# MCU1.net
KiCad netlist of a schematic drawn in Altium Designer
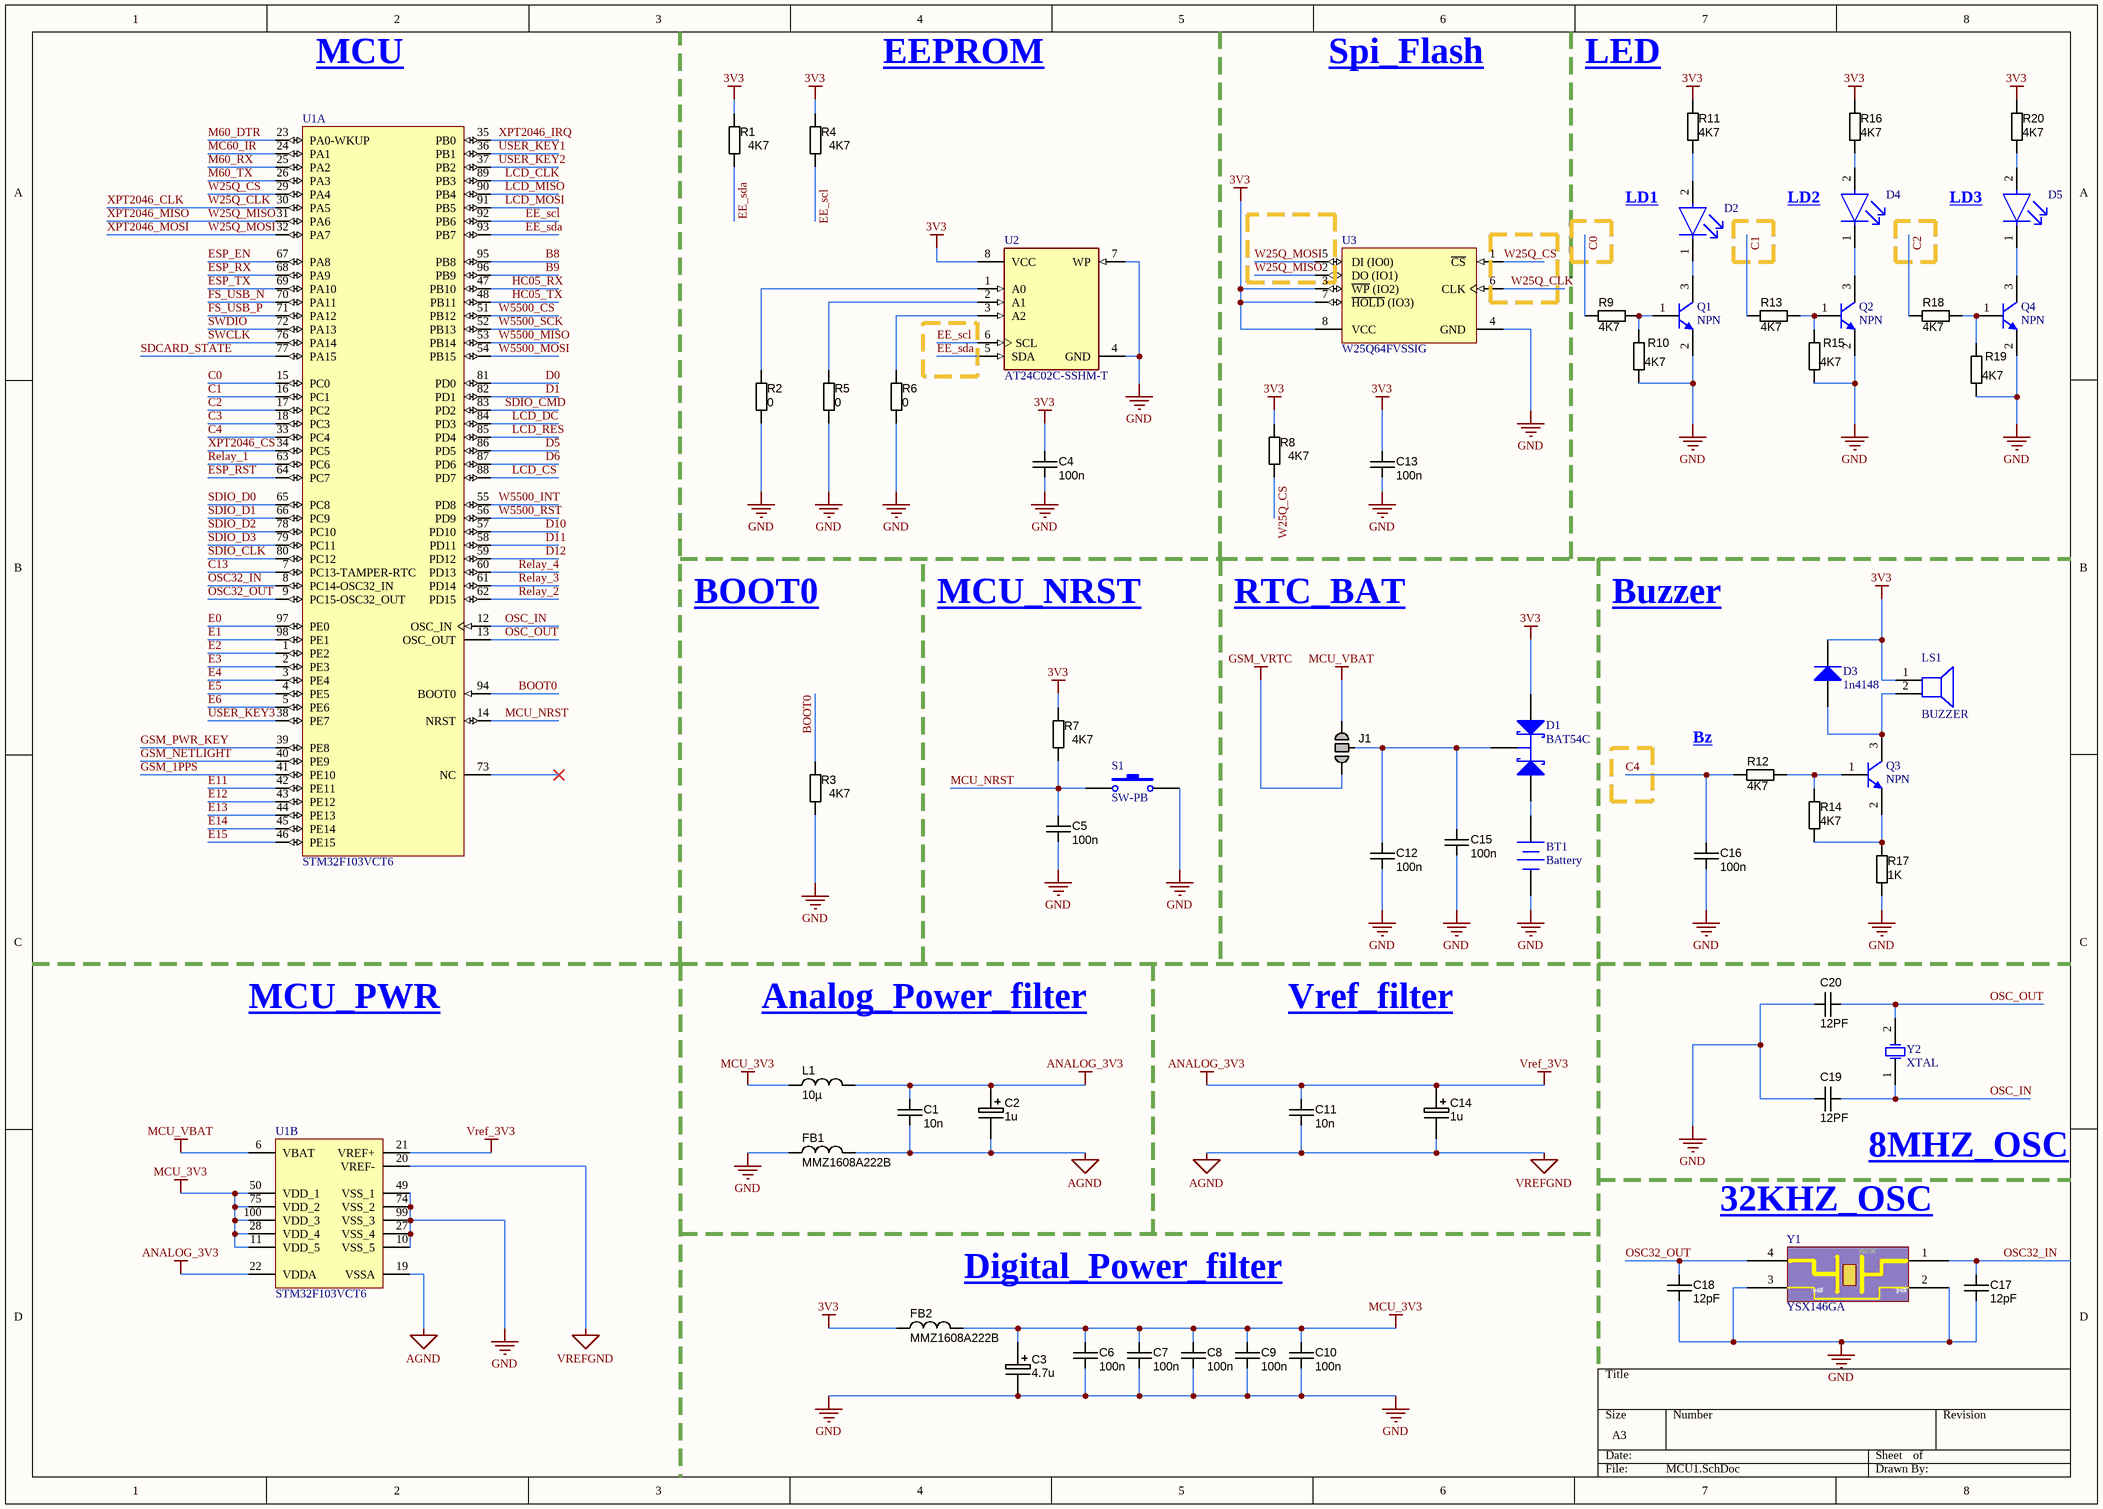
[diagram p0: MCU1.SchDoc]

(export (version "E")
  (design (tool "Eeschema 10.0.6"))
  (components
    (comp (ref "BT1")
      (value "Battery")
      (footprint "BTH1220")
      (description "Multicell Battery")
      (fields (field (name "PUBLISHER") "Altium Limited"))
      (libsource (lib "Miscellaneous Devices") (part "Battery"))
    )
    (comp (ref "C1")
      (value "10n")
      (footprint "CAPC1608X90N")
      (description "Capacitor SMD Cer 100nF 10% 50V X7R 0603")
      (fields (field (name "TOLERANCE") "±10%") (field (name "Comment") "approved sub OK"))
      (libsource (lib "PBL - Capacitors") (part "CAPC_100n_0603_X7R_50V_10%"))
    )
    (comp (ref "C2")
      (value "1u")
      (footprint "C_TN_3216")
      (description "Capacitor SMD Tantalum 10uF 10% 16V 3216-18")
      (fields (field (name "TOLERANCE") "±10%"))
      (libsource (lib "PBL - Capacitors") (part "CAPT_4u7_3216_16V"))
    )
    (comp (ref "C3")
      (value "4.7u")
      (footprint "C_TN_3528")
      (description "Capacitor SMD Tantalum 10uF 10% 16V 3216-18")
      (fields (field (name "TOLERANCE") "±10%"))
      (libsource (lib "PBL - Capacitors") (part "CAPT_4u7_3216_16V"))
    )
    (comp (ref "C4")
      (value "100n")
      (footprint "CAPC1608X90N")
      (description "Capacitor SMD Cer 100nF 10% 50V X7R 0603")
      (fields (field (name "TOLERANCE") "±10%") (field (name "Comment") "approved sub OK"))
      (libsource (lib "PBL - Capacitors") (part "CAPC_100n_0603_X7R_50V_10%"))
    )
    (comp (ref "C5")
      (value "100n")
      (footprint "CAPC1608X90N")
      (description "Capacitor SMD Cer 100nF 10% 50V X7R 0603")
      (fields (field (name "TOLERANCE") "±10%") (field (name "Comment") "approved sub OK"))
      (libsource (lib "PBL - Capacitors") (part "CAPC_100n_0603_X7R_50V_10%"))
    )
    (comp (ref "C6")
      (value "100n")
      (footprint "CAPC1608X90N")
      (description "Capacitor SMD Cer 100nF 10% 50V X7R 0603")
      (fields (field (name "TOLERANCE") "±10%") (field (name "Comment") "approved sub OK"))
      (libsource (lib "PBL - Capacitors") (part "CAPC_100n_0603_X7R_50V_10%"))
    )
    (comp (ref "C7")
      (value "100n")
      (footprint "CAPC1608X90N")
      (description "Capacitor SMD Cer 100nF 10% 50V X7R 0603")
      (fields (field (name "TOLERANCE") "±10%") (field (name "Comment") "approved sub OK"))
      (libsource (lib "PBL - Capacitors") (part "CAPC_100n_0603_X7R_50V_10%"))
    )
    (comp (ref "C8")
      (value "100n")
      (footprint "CAPC1608X90N")
      (description "Capacitor SMD Cer 100nF 10% 50V X7R 0603")
      (fields (field (name "TOLERANCE") "±10%") (field (name "Comment") "approved sub OK"))
      (libsource (lib "PBL - Capacitors") (part "CAPC_100n_0603_X7R_50V_10%"))
    )
    (comp (ref "C9")
      (value "100n")
      (footprint "CAPC1608X90N")
      (description "Capacitor SMD Cer 100nF 10% 50V X7R 0603")
      (fields (field (name "TOLERANCE") "±10%") (field (name "Comment") "approved sub OK"))
      (libsource (lib "PBL - Capacitors") (part "CAPC_100n_0603_X7R_50V_10%"))
    )
    (comp (ref "C10")
      (value "100n")
      (footprint "CAPC1608X90N")
      (description "Capacitor SMD Cer 100nF 10% 50V X7R 0603")
      (fields (field (name "TOLERANCE") "±10%") (field (name "Comment") "approved sub OK"))
      (libsource (lib "PBL - Capacitors") (part "CAPC_100n_0603_X7R_50V_10%"))
    )
    (comp (ref "C11")
      (value "10n")
      (footprint "CAPC1608X90N")
      (description "Capacitor SMD Cer 100nF 10% 50V X7R 0603")
      (fields (field (name "TOLERANCE") "±10%") (field (name "Comment") "approved sub OK"))
      (libsource (lib "PBL - Capacitors") (part "CAPC_100n_0603_X7R_50V_10%"))
    )
    (comp (ref "C12")
      (value "100n")
      (footprint "CAPC1608X90N")
      (description "Capacitor SMD Cer 100nF 10% 50V X7R 0603")
      (fields (field (name "TOLERANCE") "±10%") (field (name "Comment") "approved sub OK"))
      (libsource (lib "PBL - Capacitors") (part "CAPC_100n_0603_X7R_50V_10%"))
    )
    (comp (ref "C13")
      (value "100n")
      (footprint "CAPC1608X90N")
      (description "Capacitor SMD Cer 100nF 10% 50V X7R 0603")
      (fields (field (name "TOLERANCE") "±10%") (field (name "Comment") "approved sub OK"))
      (libsource (lib "PBL - Capacitors") (part "CAPC_100n_0603_X7R_50V_10%"))
    )
    (comp (ref "C14")
      (value "1u")
      (footprint "C_TN_3216")
      (description "Capacitor SMD Tantalum 10uF 10% 16V 3216-18")
      (fields (field (name "TOLERANCE") "±10%"))
      (libsource (lib "PBL - Capacitors") (part "CAPT_4u7_3216_16V"))
    )
    (comp (ref "C15")
      (value "100n")
      (footprint "C1206")
      (description "Capacitor SMD Cer 100nF 10% 50V X7R 0603")
      (fields (field (name "TOLERANCE") "±10%") (field (name "Comment") "approved sub OK"))
      (libsource (lib "PBL - Capacitors") (part "CAPC_100n_0603_X7R_50V_10%"))
    )
    (comp (ref "C16")
      (value "100n")
      (footprint "CAPC1608X90N")
      (description "Capacitor SMD Cer 100nF 10% 50V X7R 0603")
      (fields (field (name "TOLERANCE") "±10%") (field (name "Comment") "approved sub OK"))
      (libsource (lib "PBL - Capacitors") (part "CAPC_100n_0603_X7R_50V_10%"))
    )
    (comp (ref "C17")
      (value "12pF")
      (footprint "CAPC1608X90N")
      (description "Capacitor SMD Cer 6.8PF 10% 50V X7R 0603")
      (fields (field (name "TOLERANCE") "±10%") (field (name "Comment") "approved sub OK"))
      (libsource (lib "PBL - Capacitors") (part "CAPC_100n_0603_X7R_50V_10%"))
    )
    (comp (ref "C18")
      (value "12pF")
      (footprint "CAPC1608X90N")
      (description "Capacitor SMD Cer 6.8PF 10% 50V X7R 0603")
      (fields (field (name "TOLERANCE") "±10%") (field (name "Comment") "approved sub OK"))
      (libsource (lib "PBL - Capacitors") (part "CAPC_100n_0603_X7R_50V_10%"))
    )
    (comp (ref "C19")
      (value "12PF")
      (footprint "CAPC1608X90N")
      (description "Capacitor SMD Cer 20PF10% 50V X7R 0603")
      (fields (field (name "TOLERANCE") "±10%") (field (name "Comment") "approved sub OK"))
      (libsource (lib "PBL - Capacitors") (part "CAPC_100n_0603_X7R_50V_10%"))
    )
    (comp (ref "C20")
      (value "12PF")
      (footprint "CAPC1608X90N")
      (description "Capacitor SMD Cer 20PF10% 50V X7R 0603")
      (fields (field (name "TOLERANCE") "±10%") (field (name "Comment") "approved sub OK"))
      (libsource (lib "PBL - Capacitors") (part "CAPC_100n_0603_X7R_50V_10%"))
    )
    (comp (ref "D1")
      (value "BAT54C")
      (footprint "NXP-SOT23-3_V")
      (description "Schottky Barrier Diode, 30 V, 2 uA, -55 to 150 degC, 3-Pin SOT23, RoHS, Tape and Reel")
      (fields (field (name "MANUFACTURER") "NXP Semiconductors"))
      (libsource (lib "Altium Content Vault") (part "NXP-DSKY_A1A2K3-3"))
    )
    (comp (ref "D2")
      (value "LTST-C191TBKT")
      (footprint "FP-LTST-C191TBKT-MFG")
      (description "LED BLUE CLEAR CHIP SMD")
      (libsource (lib "Altium Content Vault") (part "8706943c75ba83719d021d2fdc84c58"))
    )
    (comp (ref "D3")
      (value "1n4148")
      (footprint "d_sod80")
      (description "Default Diode")
      (fields (field (name "PUBLISHER") "Altium Limited"))
      (libsource (lib "Miscellaneous Devices") (part "Diode"))
    )
    (comp (ref "D4")
      (value "LTST-C191TBKT")
      (footprint "FP-LTST-C191TBKT-MFG")
      (description "LED BLUE CLEAR CHIP SMD")
      (libsource (lib "Altium Content Vault") (part "8706943c75ba83719d021d2fdc84c58"))
    )
    (comp (ref "D5")
      (value "LTST-C191TBKT")
      (footprint "FP-LTST-C191TBKT-MFG")
      (description "LED BLUE CLEAR CHIP SMD")
      (libsource (lib "Altium Content Vault") (part "8706943c75ba83719d021d2fdc84c58"))
    )
    (comp (ref "FB1")
      (value "2K2 @ 100 MHz")
      (footprint "FBC1608X95N")
      (description "Ferrite bead 2.2K Ohm at 100 MHz 200mA 0603 SMD")
      (fields (field (name "MANUFACTURER PART NUMBER 1") "MMZ1608A222B"))
      (libsource (lib "PBL - Inductors") (part "FERRITE_2K2-100MHz_0603"))
    )
    (comp (ref "FB2")
      (value "2K2 @ 100 MHz")
      (footprint "FBC1608X95N")
      (description "Ferrite bead 2.2K Ohm at 100 MHz 200mA 0603 SMD")
      (fields (field (name "MANUFACTURER PART NUMBER 1") "MMZ1608A222B"))
      (libsource (lib "PBL - Inductors") (part "FERRITE_2K2-100MHz_0603"))
    )
    (comp (ref "J1")
      (value "Jumper")
      (footprint "Jump_3Way")
      (description "SMD jumper")
      (libsource (lib "PBL - Pads and Jumpers") (part "JUMP_3WAY"))
    )
    (comp (ref "L1")
      (value "10µ")
      (footprint "INDC3225X250N")
      (description "Inductor SMD Low DCR 10 µH 900mA 20% 1210")
      (fields (field (name "TOLERANCE") "±20%"))
      (libsource (lib "PBL - Inductors") (part "INDC_10u_LowRDC"))
    )
    (comp (ref "LS1")
      (value "BUZZER")
      (footprint "BZ_C12")
      (description "Loudspeaker")
      (fields (field (name "PUBLISHER") "Altium Limited"))
      (libsource (lib "Miscellaneous Devices") (part "Speaker"))
    )
    (comp (ref "Q1")
      (value "NPN")
      (footprint "SOT23-3")
      (description "NPN Bipolar Transistor")
      (fields (field (name "PUBLISHER") "Altium Limited"))
      (libsource (lib "Miscellaneous Devices") (part "NPN"))
    )
    (comp (ref "Q2")
      (value "NPN")
      (footprint "SOT23-3")
      (description "NPN Bipolar Transistor")
      (fields (field (name "PUBLISHER") "Altium Limited"))
      (libsource (lib "Miscellaneous Devices") (part "NPN"))
    )
    (comp (ref "Q3")
      (value "NPN")
      (footprint "SOT23-3")
      (description "NPN Bipolar Transistor")
      (fields (field (name "PUBLISHER") "Altium Limited"))
      (libsource (lib "Miscellaneous Devices") (part "NPN"))
    )
    (comp (ref "Q4")
      (value "NPN")
      (footprint "SOT23-3")
      (description "NPN Bipolar Transistor")
      (fields (field (name "PUBLISHER") "Altium Limited"))
      (libsource (lib "Miscellaneous Devices") (part "NPN"))
    )
    (comp (ref "R1")
      (value "4K7")
      (footprint "RESC1608X55N")
      (description "Resistor SMD chip 4.7k Ohm 0.1W 5% 0603")
      (fields (field (name "TOLERANCE") "±5%") (field (name "Comment") "Thick Film"))
      (libsource (lib "PBL - Resistors") (part "RES_4K7_0603_5%"))
    )
    (comp (ref "R2")
      (value "0")
      (footprint "RESC1608X55N")
      (description "Resistor SMD chip 0 Ohm 0.1W 5% 0603")
      (fields (field (name "TOLERANCE") "±5%") (field (name "Comment") "Thick Film"))
      (libsource (lib "") (part "RES_4K7_0603_5%_1"))
    )
    (comp (ref "R3")
      (value "4K7")
      (footprint "RESC1608X55N")
      (description "Resistor SMD chip 4.7k Ohm 0.1W 5% 0603")
      (fields (field (name "TOLERANCE") "±5%") (field (name "Comment") "Thick Film"))
      (libsource (lib "PBL - Resistors") (part "RES_4K7_0603_5%"))
    )
    (comp (ref "R4")
      (value "4K7")
      (footprint "RESC1608X55N")
      (description "Resistor SMD chip 4.7k Ohm 0.1W 5% 0603")
      (fields (field (name "TOLERANCE") "±5%") (field (name "Comment") "Thick Film"))
      (libsource (lib "PBL - Resistors") (part "RES_4K7_0603_5%"))
    )
    (comp (ref "R5")
      (value "0")
      (footprint "RESC1608X55N")
      (description "Resistor SMD chip 0 Ohm 0.1W 5% 0603")
      (fields (field (name "TOLERANCE") "±5%") (field (name "Comment") "Thick Film"))
      (libsource (lib "") (part "RES_4K7_0603_5%_1"))
    )
    (comp (ref "R6")
      (value "0")
      (footprint "RESC1608X55N")
      (description "Resistor SMD chip 0 Ohm 0.1W 5% 0603")
      (fields (field (name "TOLERANCE") "±5%") (field (name "Comment") "Thick Film"))
      (libsource (lib "") (part "RES_4K7_0603_5%_1"))
    )
    (comp (ref "R7")
      (value "4K7")
      (footprint "RESC1608X55N")
      (description "Resistor SMD chip 4.7k Ohm 0.1W 5% 0603")
      (fields (field (name "TOLERANCE") "±5%") (field (name "Comment") "Thick Film"))
      (libsource (lib "PBL - Resistors") (part "RES_4K7_0603_5%"))
    )
    (comp (ref "R8")
      (value "4K7")
      (footprint "RESC1608X55N")
      (description "Resistor SMD chip 4.7k Ohm 0.1W 5% 0603")
      (fields (field (name "TOLERANCE") "±5%") (field (name "Comment") "Thick Film"))
      (libsource (lib "PBL - Resistors") (part "RES_4K7_0603_5%"))
    )
    (comp (ref "R9")
      (value "4K7")
      (footprint "RESC1608X55N")
      (description "Resistor SMD chip 4.7k Ohm 0.1W 5% 0603")
      (fields (field (name "TOLERANCE") "±5%") (field (name "Comment") "Thick Film"))
      (libsource (lib "") (part "RES_4K7_0603_5%_2"))
    )
    (comp (ref "R10")
      (value "4K7")
      (footprint "RESC1608X55N")
      (description "Resistor SMD chip 4.7k Ohm 0.1W 5% 0603")
      (fields (field (name "TOLERANCE") "±5%") (field (name "Comment") "Thick Film"))
      (libsource (lib "") (part "RES_4K7_0603_5%_1"))
    )
    (comp (ref "R11")
      (value "4K7")
      (footprint "RESC1608X55N")
      (description "Resistor SMD chip 4.7k Ohm 0.1W 5% 0603")
      (fields (field (name "TOLERANCE") "±5%") (field (name "Comment") "Thick Film"))
      (libsource (lib "") (part "RES_4K7_0603_5%_1"))
    )
    (comp (ref "R12")
      (value "4K7")
      (footprint "RESC1608X55N")
      (description "Resistor SMD chip 4.7k Ohm 0.1W 5% 0603")
      (fields (field (name "TOLERANCE") "±5%") (field (name "Comment") "Thick Film"))
      (libsource (lib "") (part "RES_4K7_0603_5%_2"))
    )
    (comp (ref "R13")
      (value "4K7")
      (footprint "RESC1608X55N")
      (description "Resistor SMD chip 4.7k Ohm 0.1W 5% 0603")
      (fields (field (name "TOLERANCE") "±5%") (field (name "Comment") "Thick Film"))
      (libsource (lib "") (part "RES_4K7_0603_5%_2"))
    )
    (comp (ref "R14")
      (value "4K7")
      (footprint "RESC1608X55N")
      (description "Resistor SMD chip 4.7k Ohm 0.1W 5% 0603")
      (fields (field (name "TOLERANCE") "±5%") (field (name "Comment") "Thick Film"))
      (libsource (lib "") (part "RES_4K7_0603_5%_1"))
    )
    (comp (ref "R15")
      (value "4K7")
      (footprint "RESC1608X55N")
      (description "Resistor SMD chip 4.7k Ohm 0.1W 5% 0603")
      (fields (field (name "TOLERANCE") "±5%") (field (name "Comment") "Thick Film"))
      (libsource (lib "") (part "RES_4K7_0603_5%_1"))
    )
    (comp (ref "R16")
      (value "4K7")
      (footprint "RESC1608X55N")
      (description "Resistor SMD chip 4.7k Ohm 0.1W 5% 0603")
      (fields (field (name "TOLERANCE") "±5%") (field (name "Comment") "Thick Film"))
      (libsource (lib "") (part "RES_4K7_0603_5%_1"))
    )
    (comp (ref "R17")
      (value "1K")
      (footprint "RESC1608X55N")
      (description "Resistor SMD chip 4.7k Ohm 0.1W 5% 0603")
      (fields (field (name "TOLERANCE") "±5%") (field (name "Comment") "Thick Film"))
      (libsource (lib "PBL - Resistors") (part "RES_4K7_0603_5%"))
    )
    (comp (ref "R18")
      (value "4K7")
      (footprint "RESC1608X55N")
      (description "Resistor SMD chip 4.7k Ohm 0.1W 5% 0603")
      (fields (field (name "TOLERANCE") "±5%") (field (name "Comment") "Thick Film"))
      (libsource (lib "") (part "RES_4K7_0603_5%_2"))
    )
    (comp (ref "R19")
      (value "4K7")
      (footprint "RESC1608X55N")
      (description "Resistor SMD chip 4.7k Ohm 0.1W 5% 0603")
      (fields (field (name "TOLERANCE") "±5%") (field (name "Comment") "Thick Film"))
      (libsource (lib "") (part "RES_4K7_0603_5%_1"))
    )
    (comp (ref "R20")
      (value "4K7")
      (footprint "RESC1608X55N")
      (description "Resistor SMD chip 4.7k Ohm 0.1W 5% 0603")
      (fields (field (name "TOLERANCE") "±5%") (field (name "Comment") "Thick Film"))
      (libsource (lib "") (part "RES_4K7_0603_5%_1"))
    )
    (comp (ref "S1")
      (value "SW-PB")
      (footprint "SWPBS_SPST_6X3X5")
      (description "Switch")
      (fields (field (name "PUBLISHER") "Altium Limited"))
      (libsource (lib "Miscellaneous Devices") (part "SW-PB"))
    )
    (comp (ref "U1")
      (value "STM32F103VCT6")
      (footprint "STM-LQFP100_L")
      (libsource (lib "Altium Content Vault") (part "MC-ARM-STM32F103XC_D_E-SQ100"))
    )
    (comp (ref "U2")
      (value "AT24C02C-SSHM-T")
      (footprint "FP-C04-057-SN-MFG")
      (description "IC EEPROM 2K I2C 1MHZ 8SOIC")
      (fields
        (field (name "OCTOPART") "https://octopart.com/at24c02c-sshm-t-microchip-77757935")
        (field (name "MANUFACTURER") "Microchip")
      )
      (libsource (lib "Altium Content Vault") (part "10b14863ecfc9a00679244ba73e2fea"))
    )
    (comp (ref "U3")
      (value "W25Q64FVSSIG")
      (footprint "WINB-SOIC-8_M")
      (fields (field (name "MANUFACTURER") "Winbond"))
      (libsource (lib "Altium Content Vault") (part "WINB-W25Q64FVSSIG-SOIC-8"))
    )
    (comp (ref "Y1")
      (value "YSX146GA")
      (footprint "YSX146GA-32.768xTAL")
      (libsource (lib "YSX146GA") (part "YSX146GA"))
    )
    (comp (ref "Y2")
      (value "XTAL")
      (footprint "XTL_2_5032")
      (description "Crystal Oscillator")
      (fields (field (name "PUBLISHER") "Altium Limited"))
      (libsource (lib "Miscellaneous Devices") (part "XTAL"))
    )
  )
  (nets
    (net (code "1") (name "/B8") (class "Default")
      (node (ref "U1") (pin "95") (pinfunction "PB8_95") (pintype "bidirectional"))
    )
    (net (code "2") (name "/B9") (class "Default")
      (node (ref "U1") (pin "96") (pinfunction "PB9_96") (pintype "bidirectional"))
    )
    (net (code "3") (name "/BOOT0") (class "Default")
      (node (ref "R3") (pin "1") (pinfunction "1_1") (pintype "passive"))
      (node (ref "U1") (pin "94") (pinfunction "BOOT0_94") (pintype "input"))
    )
    (net (code "4") (name "/C0") (class "Default")
      (node (ref "R9") (pin "1") (pinfunction "1_1") (pintype "passive"))
      (node (ref "U1") (pin "15") (pinfunction "PC0_15") (pintype "bidirectional"))
    )
    (net (code "5") (name "/C1") (class "Default")
      (node (ref "R13") (pin "1") (pinfunction "1_1") (pintype "passive"))
      (node (ref "U1") (pin "16") (pinfunction "PC1_16") (pintype "bidirectional"))
    )
    (net (code "6") (name "/C2") (class "Default")
      (node (ref "R18") (pin "1") (pinfunction "1_1") (pintype "passive"))
      (node (ref "U1") (pin "17") (pinfunction "PC2_17") (pintype "bidirectional"))
    )
    (net (code "7") (name "/C3") (class "Default")
      (node (ref "U1") (pin "18") (pinfunction "PC3_18") (pintype "bidirectional"))
    )
    (net (code "8") (name "/C4") (class "Default")
      (node (ref "C16") (pin "1") (pintype "passive"))
      (node (ref "R12") (pin "1") (pinfunction "1_1") (pintype "passive"))
      (node (ref "U1") (pin "33") (pinfunction "PC4_33") (pintype "bidirectional"))
    )
    (net (code "9") (name "/C13") (class "Default")
      (node (ref "U1") (pin "7") (pinfunction "PC13-TAMPER-RTC_7") (pintype "bidirectional"))
    )
    (net (code "10") (name "/D0") (class "Default")
      (node (ref "U1") (pin "81") (pinfunction "PD0_81") (pintype "bidirectional"))
    )
    (net (code "11") (name "/D1") (class "Default")
      (node (ref "U1") (pin "82") (pinfunction "PD1_82") (pintype "bidirectional"))
    )
    (net (code "12") (name "/D5") (class "Default")
      (node (ref "U1") (pin "86") (pinfunction "PD5_86") (pintype "bidirectional"))
    )
    (net (code "13") (name "/D6") (class "Default")
      (node (ref "U1") (pin "87") (pinfunction "PD6_87") (pintype "bidirectional"))
    )
    (net (code "14") (name "/D10") (class "Default")
      (node (ref "U1") (pin "57") (pinfunction "PD10_57") (pintype "bidirectional"))
    )
    (net (code "15") (name "/D11") (class "Default")
      (node (ref "U1") (pin "58") (pinfunction "PD11_58") (pintype "bidirectional"))
    )
    (net (code "16") (name "/D12") (class "Default")
      (node (ref "U1") (pin "59") (pinfunction "PD12_59") (pintype "bidirectional"))
    )
    (net (code "17") (name "/E0") (class "Default")
      (node (ref "U1") (pin "97") (pinfunction "PE0_97") (pintype "bidirectional"))
    )
    (net (code "18") (name "/E1") (class "Default")
      (node (ref "U1") (pin "98") (pinfunction "PE1_98") (pintype "bidirectional"))
    )
    (net (code "19") (name "/E2") (class "Default")
      (node (ref "U1") (pin "1") (pinfunction "PE2_1") (pintype "bidirectional"))
    )
    (net (code "20") (name "/E3") (class "Default")
      (node (ref "U1") (pin "2") (pinfunction "PE3_2") (pintype "bidirectional"))
    )
    (net (code "21") (name "/E4") (class "Default")
      (node (ref "U1") (pin "3") (pinfunction "PE4_3") (pintype "bidirectional"))
    )
    (net (code "22") (name "/E5") (class "Default")
      (node (ref "U1") (pin "4") (pinfunction "PE5_4") (pintype "bidirectional"))
    )
    (net (code "23") (name "/E6") (class "Default")
      (node (ref "U1") (pin "5") (pinfunction "PE6_5") (pintype "bidirectional"))
    )
    (net (code "24") (name "/E11") (class "Default")
      (node (ref "U1") (pin "42") (pinfunction "PE11_42") (pintype "bidirectional"))
    )
    (net (code "25") (name "/E12") (class "Default")
      (node (ref "U1") (pin "43") (pinfunction "PE12_43") (pintype "bidirectional"))
    )
    (net (code "26") (name "/E13") (class "Default")
      (node (ref "U1") (pin "44") (pinfunction "PE13_44") (pintype "bidirectional"))
    )
    (net (code "27") (name "/E14") (class "Default")
      (node (ref "U1") (pin "45") (pinfunction "PE14_45") (pintype "bidirectional"))
    )
    (net (code "28") (name "/E15") (class "Default")
      (node (ref "U1") (pin "46") (pinfunction "PE15_46") (pintype "bidirectional"))
    )
    (net (code "29") (name "/EE_scl") (class "Default")
      (node (ref "R4") (pin "2") (pinfunction "2_2") (pintype "passive"))
      (node (ref "U1") (pin "92") (pinfunction "PB6_92") (pintype "bidirectional"))
      (node (ref "U2") (pin "6") (pinfunction "SCL_6") (pintype "input"))
    )
    (net (code "30") (name "/EE_sda") (class "Default")
      (node (ref "R1") (pin "2") (pinfunction "2_2") (pintype "passive"))
      (node (ref "U1") (pin "93") (pinfunction "PB7_93") (pintype "bidirectional"))
      (node (ref "U2") (pin "5") (pinfunction "SDA_5") (pintype "input"))
    )
    (net (code "31") (name "/ESP_EN") (class "Default")
      (node (ref "U1") (pin "67") (pinfunction "PA8_67") (pintype "bidirectional"))
    )
    (net (code "32") (name "/ESP_RST") (class "Default")
      (node (ref "U1") (pin "64") (pinfunction "PC7_64") (pintype "bidirectional"))
    )
    (net (code "33") (name "/ESP_RX") (class "Default")
      (node (ref "U1") (pin "68") (pinfunction "PA9_68") (pintype "bidirectional"))
    )
    (net (code "34") (name "/ESP_TX") (class "Default")
      (node (ref "U1") (pin "69") (pinfunction "PA10_69") (pintype "bidirectional"))
    )
    (net (code "35") (name "/FS_USB_N") (class "Default")
      (node (ref "U1") (pin "70") (pinfunction "PA11_70") (pintype "bidirectional"))
    )
    (net (code "36") (name "/FS_USB_P") (class "Default")
      (node (ref "U1") (pin "71") (pinfunction "PA12_71") (pintype "bidirectional"))
    )
    (net (code "37") (name "/GSM_1PPS") (class "Default")
      (node (ref "U1") (pin "41") (pinfunction "PE10_41") (pintype "bidirectional"))
    )
    (net (code "38") (name "/GSM_NETLIGHT") (class "Default")
      (node (ref "U1") (pin "40") (pinfunction "PE9_40") (pintype "bidirectional"))
    )
    (net (code "39") (name "/GSM_PWR_KEY") (class "Default")
      (node (ref "U1") (pin "39") (pinfunction "PE8_39") (pintype "bidirectional"))
    )
    (net (code "40") (name "/HC05_RX") (class "Default")
      (node (ref "U1") (pin "47") (pinfunction "PB10_47") (pintype "bidirectional"))
    )
    (net (code "41") (name "/HC05_TX") (class "Default")
      (node (ref "U1") (pin "48") (pinfunction "PB11_48") (pintype "bidirectional"))
    )
    (net (code "42") (name "/LCD_CLK") (class "Default")
      (node (ref "U1") (pin "89") (pinfunction "PB3_89") (pintype "bidirectional"))
    )
    (net (code "43") (name "/LCD_CS") (class "Default")
      (node (ref "U1") (pin "88") (pinfunction "PD7_88") (pintype "bidirectional"))
    )
    (net (code "44") (name "/LCD_DC") (class "Default")
      (node (ref "U1") (pin "84") (pinfunction "PD3_84") (pintype "bidirectional"))
    )
    (net (code "45") (name "/LCD_MISO") (class "Default")
      (node (ref "U1") (pin "90") (pinfunction "PB4_90") (pintype "bidirectional"))
    )
    (net (code "46") (name "/LCD_MOSI") (class "Default")
      (node (ref "U1") (pin "91") (pinfunction "PB5_91") (pintype "bidirectional"))
    )
    (net (code "47") (name "/LCD_RES") (class "Default")
      (node (ref "U1") (pin "85") (pinfunction "PD4_85") (pintype "bidirectional"))
    )
    (net (code "48") (name "/M60_DTR") (class "Default")
      (node (ref "U1") (pin "23") (pinfunction "PA0-WKUP_23") (pintype "bidirectional"))
    )
    (net (code "49") (name "/M60_RX") (class "Default")
      (node (ref "U1") (pin "25") (pinfunction "PA2_25") (pintype "bidirectional"))
    )
    (net (code "50") (name "/M60_TX") (class "Default")
      (node (ref "U1") (pin "26") (pinfunction "PA3_26") (pintype "bidirectional"))
    )
    (net (code "51") (name "/MC60_IR") (class "Default")
      (node (ref "U1") (pin "24") (pinfunction "PA1_24") (pintype "bidirectional"))
    )
    (net (code "52") (name "/MCU_NRST") (class "Default")
      (node (ref "C5") (pin "1") (pintype "passive"))
      (node (ref "R7") (pin "2") (pinfunction "2_2") (pintype "passive"))
      (node (ref "S1") (pin "1") (pinfunction "1_1") (pintype "passive"))
      (node (ref "U1") (pin "14") (pinfunction "NRST_14") (pintype "bidirectional"))
    )
    (net (code "53") (name "/OSC32_IN") (class "Default")
      (node (ref "C17") (pin "2") (pintype "passive"))
      (node (ref "U1") (pin "8") (pinfunction "PC14-OSC32_IN_8") (pintype "bidirectional"))
      (node (ref "Y1") (pin "1") (pinfunction "1_1") (pintype "passive"))
    )
    (net (code "54") (name "/OSC32_OUT") (class "Default")
      (node (ref "C18") (pin "2") (pintype "passive"))
      (node (ref "U1") (pin "9") (pinfunction "PC15-OSC32_OUT_9") (pintype "bidirectional"))
      (node (ref "Y1") (pin "4") (pinfunction "4_4") (pintype "passive"))
    )
    (net (code "55") (name "/OSC_IN") (class "Default")
      (node (ref "C19") (pin "2") (pintype "passive"))
      (node (ref "U1") (pin "12") (pinfunction "OSC_IN_12") (pintype "input"))
      (node (ref "Y2") (pin "1") (pinfunction "OSC1_1") (pintype "passive"))
    )
    (net (code "56") (name "/OSC_OUT") (class "Default")
      (node (ref "C20") (pin "2") (pintype "passive"))
      (node (ref "U1") (pin "13") (pinfunction "OSC_OUT_13") (pintype "passive"))
      (node (ref "Y2") (pin "2") (pinfunction "OSC2_2") (pintype "passive"))
    )
    (net (code "57") (name "/Relay_1") (class "Default")
      (node (ref "U1") (pin "63") (pinfunction "PC6_63") (pintype "bidirectional"))
    )
    (net (code "58") (name "/Relay_2") (class "Default")
      (node (ref "U1") (pin "62") (pinfunction "PD15_62") (pintype "bidirectional"))
    )
    (net (code "59") (name "/Relay_3") (class "Default")
      (node (ref "U1") (pin "61") (pinfunction "PD14_61") (pintype "bidirectional"))
    )
    (net (code "60") (name "/Relay_4") (class "Default")
      (node (ref "U1") (pin "60") (pinfunction "PD13_60") (pintype "bidirectional"))
    )
    (net (code "61") (name "/SDCARD_STATE") (class "Default")
      (node (ref "U1") (pin "77") (pinfunction "PA15_77") (pintype "bidirectional"))
    )
    (net (code "62") (name "/SDIO_CLK") (class "Default")
      (node (ref "U1") (pin "80") (pinfunction "PC12_80") (pintype "bidirectional"))
    )
    (net (code "63") (name "/SDIO_CMD") (class "Default")
      (node (ref "U1") (pin "83") (pinfunction "PD2_83") (pintype "bidirectional"))
    )
    (net (code "64") (name "/SDIO_D0") (class "Default")
      (node (ref "U1") (pin "65") (pinfunction "PC8_65") (pintype "bidirectional"))
    )
    (net (code "65") (name "/SDIO_D1") (class "Default")
      (node (ref "U1") (pin "66") (pinfunction "PC9_66") (pintype "bidirectional"))
    )
    (net (code "66") (name "/SDIO_D2") (class "Default")
      (node (ref "U1") (pin "78") (pinfunction "PC10_78") (pintype "bidirectional"))
    )
    (net (code "67") (name "/SDIO_D3") (class "Default")
      (node (ref "U1") (pin "79") (pinfunction "PC11_79") (pintype "bidirectional"))
    )
    (net (code "68") (name "/SWCLK") (class "Default")
      (node (ref "U1") (pin "76") (pinfunction "PA14_76") (pintype "bidirectional"))
    )
    (net (code "69") (name "/SWDIO") (class "Default")
      (node (ref "U1") (pin "72") (pinfunction "PA13_72") (pintype "bidirectional"))
    )
    (net (code "70") (name "/USER_KEY1") (class "Default")
      (node (ref "U1") (pin "36") (pinfunction "PB1_36") (pintype "bidirectional"))
    )
    (net (code "71") (name "/USER_KEY2") (class "Default")
      (node (ref "U1") (pin "37") (pinfunction "PB2_37") (pintype "bidirectional"))
    )
    (net (code "72") (name "/USER_KEY3") (class "Default")
      (node (ref "U1") (pin "38") (pinfunction "PE7_38") (pintype "bidirectional"))
    )
    (net (code "73") (name "/W25Q_CLK") (class "Default")
      (node (ref "U1") (pin "30") (pinfunction "PA5_30") (pintype "bidirectional"))
      (node (ref "U3") (pin "6") (pinfunction "CLK_6") (pintype "input"))
    )
    (net (code "74") (name "/W25Q_CS") (class "Default")
      (node (ref "R8") (pin "2") (pinfunction "2_2") (pintype "passive"))
      (node (ref "U1") (pin "29") (pinfunction "PA4_29") (pintype "bidirectional"))
      (node (ref "U3") (pin "1") (pinfunction "~{CS}_1") (pintype "input"))
    )
    (net (code "75") (name "/W25Q_MISO") (class "Default")
      (node (ref "U1") (pin "31") (pinfunction "PA6_31") (pintype "bidirectional"))
      (node (ref "U3") (pin "2") (pinfunction "DO_(IO1)_2") (pintype "bidirectional"))
    )
    (net (code "76") (name "/W25Q_MOSI") (class "Default")
      (node (ref "U1") (pin "32") (pinfunction "PA7_32") (pintype "bidirectional"))
      (node (ref "U3") (pin "5") (pinfunction "DI_(IO0)_5") (pintype "bidirectional"))
    )
    (net (code "77") (name "/W5500_CS") (class "Default")
      (node (ref "U1") (pin "51") (pinfunction "PB12_51") (pintype "bidirectional"))
    )
    (net (code "78") (name "/W5500_INT") (class "Default")
      (node (ref "U1") (pin "55") (pinfunction "PD8_55") (pintype "bidirectional"))
    )
    (net (code "79") (name "/W5500_MISO") (class "Default")
      (node (ref "U1") (pin "53") (pinfunction "PB14_53") (pintype "bidirectional"))
    )
    (net (code "80") (name "/W5500_MOSI") (class "Default")
      (node (ref "U1") (pin "54") (pinfunction "PB15_54") (pintype "bidirectional"))
    )
    (net (code "81") (name "/W5500_RST") (class "Default")
      (node (ref "U1") (pin "56") (pinfunction "PD9_56") (pintype "bidirectional"))
    )
    (net (code "82") (name "/W5500_SCK") (class "Default")
      (node (ref "U1") (pin "52") (pinfunction "PB13_52") (pintype "bidirectional"))
    )
    (net (code "83") (name "/XPT2046_CS") (class "Default")
      (node (ref "U1") (pin "34") (pinfunction "PC5_34") (pintype "bidirectional"))
    )
    (net (code "84") (name "/XPT2046_IRQ") (class "Default")
      (node (ref "U1") (pin "35") (pinfunction "PB0_35") (pintype "bidirectional"))
    )
    (net (code "85") (name "3V3") (class "Default")
      (node (ref "C13") (pin "1") (pintype "passive"))
      (node (ref "C4") (pin "1") (pintype "passive"))
      (node (ref "D1") (pin "2") (pinfunction "A_2") (pintype "passive"))
      (node (ref "D3") (pin "2") (pinfunction "K_2") (pintype "passive"))
      (node (ref "FB2") (pin "1") (pinfunction "1_1") (pintype "passive"))
      (node (ref "LS1") (pin "1") (pinfunction "1_1") (pintype "passive"))
      (node (ref "R1") (pin "1") (pinfunction "1_1") (pintype "passive"))
      (node (ref "R11") (pin "2") (pinfunction "2_2") (pintype "passive"))
      (node (ref "R16") (pin "2") (pinfunction "2_2") (pintype "passive"))
      (node (ref "R20") (pin "2") (pinfunction "2_2") (pintype "passive"))
      (node (ref "R4") (pin "1") (pinfunction "1_1") (pintype "passive"))
      (node (ref "R7") (pin "1") (pinfunction "1_1") (pintype "passive"))
      (node (ref "R8") (pin "1") (pinfunction "1_1") (pintype "passive"))
      (node (ref "U2") (pin "8") (pinfunction "VCC_8") (pintype "power_in"))
      (node (ref "U3") (pin "3") (pinfunction "~{WP}_(IO2)_3") (pintype "bidirectional"))
      (node (ref "U3") (pin "7") (pinfunction "~{HOLD}_(IO3)_7") (pintype "bidirectional"))
      (node (ref "U3") (pin "8") (pinfunction "VCC_8") (pintype "power_in"))
    )
    (net (code "86") (name "AGND") (class "Default")
      (node (ref "C1") (pin "2") (pintype "passive"))
      (node (ref "C11") (pin "2") (pintype "passive"))
      (node (ref "C14") (pin "2") (pintype "passive"))
      (node (ref "C2") (pin "2") (pintype "passive"))
      (node (ref "FB1") (pin "2") (pinfunction "2_2") (pintype "passive"))
      (node (ref "U1") (pin "19") (pinfunction "VSSA_19") (pintype "power_in"))
      (node (ref "U1") (pin "20") (pinfunction "VREF-_20") (pintype "power_in"))
    )
    (net (code "87") (name "ANALOG_3V3") (class "Default")
      (node (ref "C1") (pin "1") (pintype "passive"))
      (node (ref "C11") (pin "1") (pintype "passive"))
      (node (ref "C14") (pin "1") (pintype "passive"))
      (node (ref "C2") (pin "1") (pintype "passive"))
      (node (ref "L1") (pin "2") (pinfunction "2_2") (pintype "passive"))
      (node (ref "U1") (pin "21") (pinfunction "VREF+_21") (pintype "power_in"))
      (node (ref "U1") (pin "22") (pinfunction "VDDA_22") (pintype "power_in"))
    )
    (net (code "88") (name "GND") (class "Default")
      (node (ref "BT1") (pin "2") (pinfunction "-_2") (pintype "passive"))
      (node (ref "C10") (pin "2") (pintype "passive"))
      (node (ref "C12") (pin "2") (pintype "passive"))
      (node (ref "C13") (pin "2") (pintype "passive"))
      (node (ref "C15") (pin "2") (pintype "passive"))
      (node (ref "C16") (pin "2") (pintype "passive"))
      (node (ref "C17") (pin "1") (pintype "passive"))
      (node (ref "C18") (pin "1") (pintype "passive"))
      (node (ref "C19") (pin "1") (pintype "passive"))
      (node (ref "C20") (pin "1") (pintype "passive"))
      (node (ref "C3") (pin "2") (pintype "passive"))
      (node (ref "C4") (pin "2") (pintype "passive"))
      (node (ref "C5") (pin "2") (pintype "passive"))
      (node (ref "C6") (pin "2") (pintype "passive"))
      (node (ref "C7") (pin "2") (pintype "passive"))
      (node (ref "C8") (pin "2") (pintype "passive"))
      (node (ref "C9") (pin "2") (pintype "passive"))
      (node (ref "FB1") (pin "1") (pinfunction "1_1") (pintype "passive"))
      (node (ref "Q1") (pin "2") (pinfunction "E_2") (pintype "passive"))
      (node (ref "Q2") (pin "2") (pinfunction "E_2") (pintype "passive"))
      (node (ref "Q4") (pin "2") (pinfunction "E_2") (pintype "passive"))
      (node (ref "R10") (pin "1") (pinfunction "1_1") (pintype "passive"))
      (node (ref "R15") (pin "1") (pinfunction "1_1") (pintype "passive"))
      (node (ref "R17") (pin "2") (pinfunction "2_2") (pintype "passive"))
      (node (ref "R19") (pin "1") (pinfunction "1_1") (pintype "passive"))
      (node (ref "R2") (pin "1") (pinfunction "1_1") (pintype "passive"))
      (node (ref "R3") (pin "2") (pinfunction "2_2") (pintype "passive"))
      (node (ref "R5") (pin "1") (pinfunction "1_1") (pintype "passive"))
      (node (ref "R6") (pin "1") (pinfunction "1_1") (pintype "passive"))
      (node (ref "S1") (pin "2") (pinfunction "2_2") (pintype "passive"))
      (node (ref "U1") (pin "10") (pinfunction "VSS_5_10") (pintype "power_in"))
      (node (ref "U1") (pin "27") (pinfunction "VSS_4_27") (pintype "power_in"))
      (node (ref "U1") (pin "49") (pinfunction "VSS_1_49") (pintype "power_in"))
      (node (ref "U1") (pin "74") (pinfunction "VSS_2_74") (pintype "power_in"))
      (node (ref "U1") (pin "99") (pinfunction "VSS_3_99") (pintype "power_in"))
      (node (ref "U2") (pin "4") (pinfunction "GND_4") (pintype "power_in"))
      (node (ref "U2") (pin "7") (pinfunction "WP_7") (pintype "input"))
      (node (ref "U3") (pin "4") (pinfunction "GND_4") (pintype "power_in"))
      (node (ref "Y1") (pin "2") (pinfunction "2_2") (pintype "passive"))
      (node (ref "Y1") (pin "3") (pinfunction "3_3") (pintype "passive"))
    )
    (net (code "89") (name "GSM_VRTC") (class "Default")
      (node (ref "J1") (pin "1") (pinfunction "1_1") (pintype "passive"))
    )
    (net (code "90") (name "MCU_3V3") (class "Default")
      (node (ref "C10") (pin "1") (pintype "passive"))
      (node (ref "C3") (pin "1") (pintype "passive"))
      (node (ref "C6") (pin "1") (pintype "passive"))
      (node (ref "C7") (pin "1") (pintype "passive"))
      (node (ref "C8") (pin "1") (pintype "passive"))
      (node (ref "C9") (pin "1") (pintype "passive"))
      (node (ref "FB2") (pin "2") (pinfunction "2_2") (pintype "passive"))
      (node (ref "L1") (pin "1") (pinfunction "1_1") (pintype "passive"))
      (node (ref "U1") (pin "100") (pinfunction "VDD_3_100") (pintype "power_in"))
      (node (ref "U1") (pin "11") (pinfunction "VDD_5_11") (pintype "power_in"))
      (node (ref "U1") (pin "28") (pinfunction "VDD_4_28") (pintype "power_in"))
      (node (ref "U1") (pin "50") (pinfunction "VDD_1_50") (pintype "power_in"))
      (node (ref "U1") (pin "75") (pinfunction "VDD_2_75") (pintype "power_in"))
    )
    (net (code "91") (name "MCU_VBAT") (class "Default")
      (node (ref "J1") (pin "3") (pinfunction "3_3") (pintype "passive"))
      (node (ref "U1") (pin "6") (pinfunction "VBAT_6") (pintype "power_in"))
    )
    (net (code "92") (name "Net-(BT1-+)") (class "Default")
      (node (ref "BT1") (pin "1") (pinfunction "+_1") (pintype "passive"))
      (node (ref "D1") (pin "1") (pinfunction "A_1") (pintype "passive"))
    )
    (net (code "93") (name "Net-(D1-K)") (class "Default")
      (node (ref "C12") (pin "1") (pintype "passive"))
      (node (ref "C15") (pin "1") (pintype "passive"))
      (node (ref "D1") (pin "3") (pinfunction "K_3") (pintype "passive"))
      (node (ref "J1") (pin "2") (pinfunction "2_2") (pintype "passive"))
    )
    (net (code "94") (name "Net-(D2-A)") (class "Default")
      (node (ref "D2") (pin "2") (pinfunction "A_2") (pintype "passive"))
      (node (ref "R11") (pin "1") (pinfunction "1_1") (pintype "passive"))
    )
    (net (code "95") (name "Net-(D2-C)") (class "Default")
      (node (ref "D2") (pin "1") (pinfunction "C_1") (pintype "passive"))
      (node (ref "Q1") (pin "3") (pinfunction "C_3") (pintype "passive"))
    )
    (net (code "96") (name "Net-(D3-A)") (class "Default")
      (node (ref "D3") (pin "1") (pinfunction "A_1") (pintype "passive"))
      (node (ref "LS1") (pin "2") (pinfunction "2_2") (pintype "passive"))
      (node (ref "Q3") (pin "3") (pinfunction "C_3") (pintype "passive"))
    )
    (net (code "97") (name "Net-(D4-A)") (class "Default")
      (node (ref "D4") (pin "2") (pinfunction "A_2") (pintype "passive"))
      (node (ref "R16") (pin "1") (pinfunction "1_1") (pintype "passive"))
    )
    (net (code "98") (name "Net-(D4-C)") (class "Default")
      (node (ref "D4") (pin "1") (pinfunction "C_1") (pintype "passive"))
      (node (ref "Q2") (pin "3") (pinfunction "C_3") (pintype "passive"))
    )
    (net (code "99") (name "Net-(D5-A)") (class "Default")
      (node (ref "D5") (pin "2") (pinfunction "A_2") (pintype "passive"))
      (node (ref "R20") (pin "1") (pinfunction "1_1") (pintype "passive"))
    )
    (net (code "100") (name "Net-(D5-C)") (class "Default")
      (node (ref "D5") (pin "1") (pinfunction "C_1") (pintype "passive"))
      (node (ref "Q4") (pin "3") (pinfunction "C_3") (pintype "passive"))
    )
    (net (code "101") (name "Net-(Q1-B)") (class "Default")
      (node (ref "Q1") (pin "1") (pinfunction "B_1") (pintype "passive"))
      (node (ref "R10") (pin "2") (pinfunction "2_2") (pintype "passive"))
      (node (ref "R9") (pin "2") (pinfunction "2_2") (pintype "passive"))
    )
    (net (code "102") (name "Net-(Q2-B)") (class "Default")
      (node (ref "Q2") (pin "1") (pinfunction "B_1") (pintype "passive"))
      (node (ref "R13") (pin "2") (pinfunction "2_2") (pintype "passive"))
      (node (ref "R15") (pin "2") (pinfunction "2_2") (pintype "passive"))
    )
    (net (code "103") (name "Net-(Q3-B)") (class "Default")
      (node (ref "Q3") (pin "1") (pinfunction "B_1") (pintype "passive"))
      (node (ref "R12") (pin "2") (pinfunction "2_2") (pintype "passive"))
      (node (ref "R14") (pin "2") (pinfunction "2_2") (pintype "passive"))
    )
    (net (code "104") (name "Net-(Q3-E)") (class "Default")
      (node (ref "Q3") (pin "2") (pinfunction "E_2") (pintype "passive"))
      (node (ref "R14") (pin "1") (pinfunction "1_1") (pintype "passive"))
      (node (ref "R17") (pin "1") (pinfunction "1_1") (pintype "passive"))
    )
    (net (code "105") (name "Net-(Q4-B)") (class "Default")
      (node (ref "Q4") (pin "1") (pinfunction "B_1") (pintype "passive"))
      (node (ref "R18") (pin "2") (pinfunction "2_2") (pintype "passive"))
      (node (ref "R19") (pin "2") (pinfunction "2_2") (pintype "passive"))
    )
    (net (code "106") (name "Net-(U2-A0)") (class "Default")
      (node (ref "R2") (pin "2") (pinfunction "2_2") (pintype "passive"))
      (node (ref "U2") (pin "1") (pinfunction "A0_1") (pintype "input"))
    )
    (net (code "107") (name "Net-(U2-A1)") (class "Default")
      (node (ref "R5") (pin "2") (pinfunction "2_2") (pintype "passive"))
      (node (ref "U2") (pin "2") (pinfunction "A1_2") (pintype "input"))
    )
    (net (code "108") (name "Net-(U2-A2)") (class "Default")
      (node (ref "R6") (pin "2") (pinfunction "2_2") (pintype "passive"))
      (node (ref "U2") (pin "3") (pinfunction "A2_3") (pintype "input"))
    )
    (net (code "109") (name "unconnected-(U1A-NC-Pad73)") (class "Default")
      (node (ref "U1") (pin "73") (pinfunction "NC_73") (pintype "passive+no_connect"))
    )
  )
)
